# Sheet_1_2026-02-17_1.net
KiCad netlist of a schematic drawn in Altium Designer
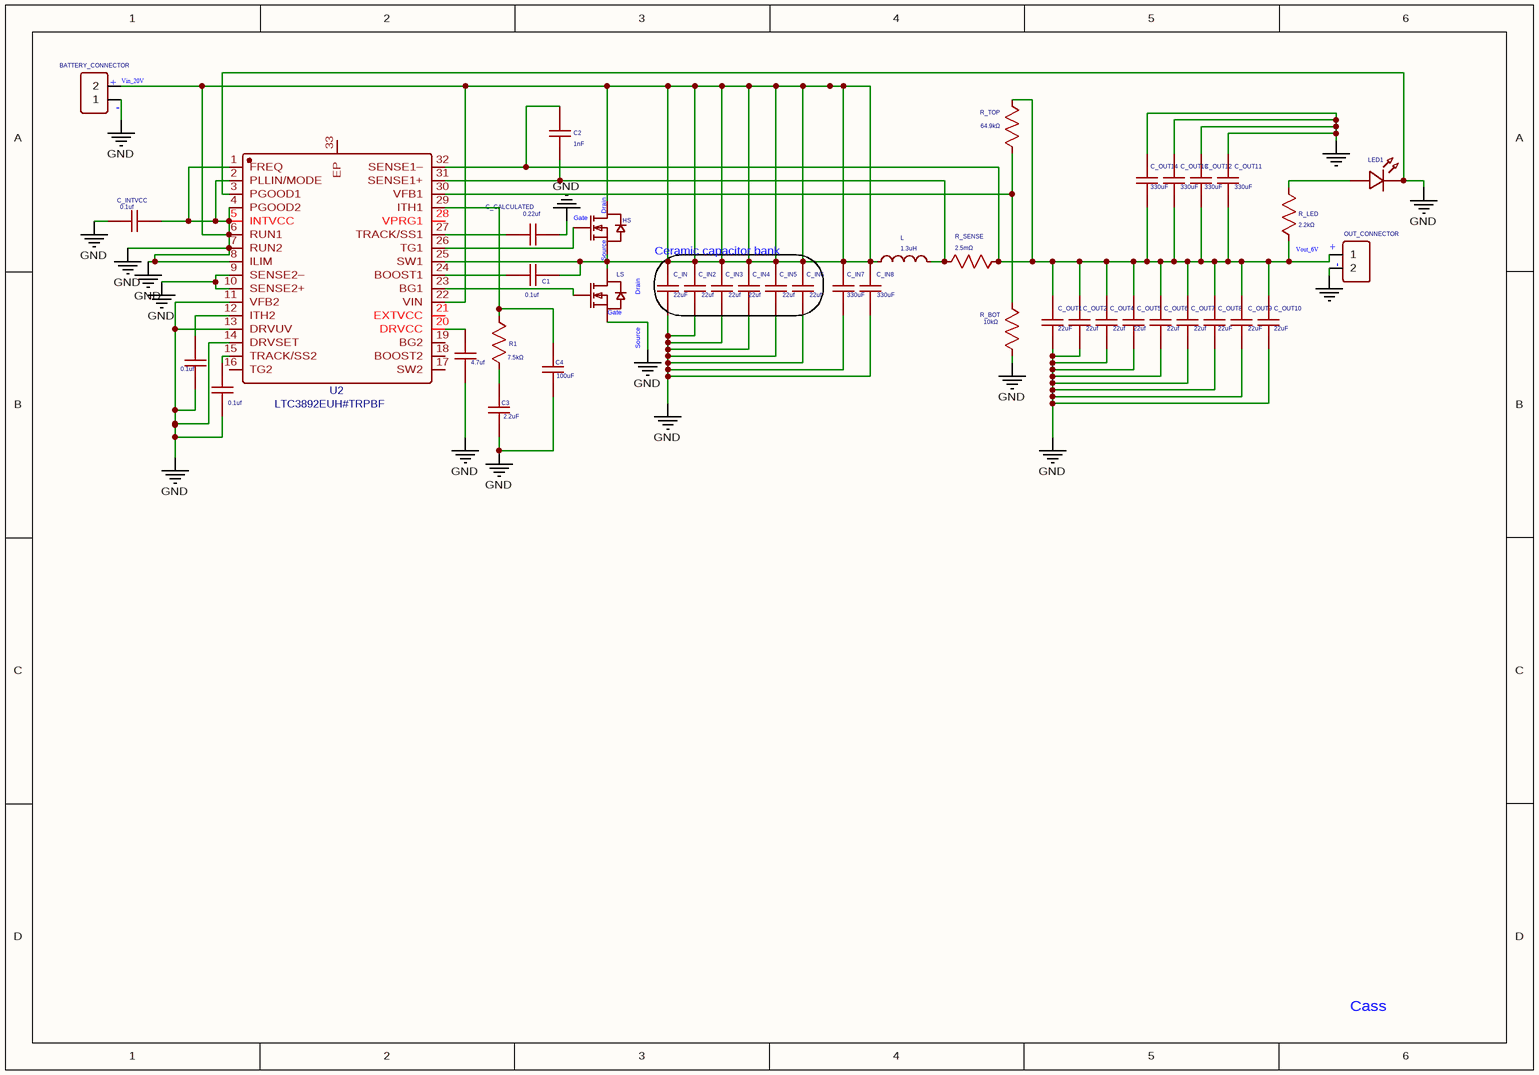
[diagram p0: Sheet_1_2026-02-17 (1).schdoc]

(export (version "E")
  (design (tool "Eeschema 10.0.6"))
  (components
    (comp (ref "BATTERY_CONNECTOR")
      (value "CONN-TH_2P-P5.00")
      (footprint "CONN-TH_2P-P5.00")
      (fields (field (name "CONTRIBUTOR") "LCEDA_Lib"))
      (libsource (lib "altium-import") (part "root_2_CONN-TH_2P-P5.00_"))
    )
    (comp (ref "C1")
      (value "0.1uf")
      (footprint "C0603")
      (fields (field (name "CONTRIBUTOR") "LCEDA_Lib"))
      (libsource (lib "altium-import") (part "root_2_0.1uf_"))
    )
    (comp (ref "C2")
      (value "1nF")
      (footprint "C0603")
      (fields (field (name "CONTRIBUTOR") "LCEDA_Lib"))
      (libsource (lib "altium-import") (part "root_1_1nF_"))
    )
    (comp (ref "C3")
      (value "2.2uF")
      (footprint "C0603")
      (fields (field (name "CONTRIBUTOR") "LCEDA_Lib"))
      (libsource (lib "altium-import") (part "root_1_2.2uF_"))
    )
    (comp (ref "C4")
      (value "100uF")
      (footprint "C0603")
      (fields (field (name "CONTRIBUTOR") "LCEDA_Lib"))
      (libsource (lib "altium-import") (part "root_3_100uF_"))
    )
    (comp (ref "C_CALCULATED")
      (value "0.22uf")
      (footprint "C0603")
      (fields (field (name "CONTRIBUTOR") "LCEDA_Lib"))
      (libsource (lib "altium-import") (part "root_0_0.22uf_"))
    )
    (comp (ref "C_DRVCC")
      (value "4.7uf")
      (footprint "C0603")
      (fields (field (name "CONTRIBUTOR") "LCEDA_Lib"))
      (libsource (lib "altium-import") (part "root_1_4.7uf_"))
    )
    (comp (ref "C_IN")
      (value "22uF")
      (footprint "C0603")
      (fields (field (name "CONTRIBUTOR") "LCEDA_Lib"))
      (libsource (lib "altium-import") (part "root_1_22uF_"))
    )
    (comp (ref "C_IN2")
      (value "22uf")
      (footprint "C0603")
      (fields (field (name "CONTRIBUTOR") "LCEDA_Lib"))
      (libsource (lib "altium-import") (part "root_1_22uf_"))
    )
    (comp (ref "C_IN3")
      (value "22uf")
      (footprint "C0603")
      (fields (field (name "CONTRIBUTOR") "LCEDA_Lib"))
      (libsource (lib "altium-import") (part "root_1_22uf_"))
    )
    (comp (ref "C_IN4")
      (value "22uf")
      (footprint "C0603")
      (fields (field (name "CONTRIBUTOR") "LCEDA_Lib"))
      (libsource (lib "altium-import") (part "root_1_22uf_"))
    )
    (comp (ref "C_IN5")
      (value "22uf")
      (footprint "C0603")
      (fields (field (name "CONTRIBUTOR") "LCEDA_Lib"))
      (libsource (lib "altium-import") (part "root_1_22uf_"))
    )
    (comp (ref "C_IN6")
      (value "22uf")
      (footprint "C0603")
      (fields (field (name "CONTRIBUTOR") "LCEDA_Lib"))
      (libsource (lib "altium-import") (part "root_1_22uf_"))
    )
    (comp (ref "C_IN7")
      (value "330uF")
      (footprint "C0603")
      (fields (field (name "CONTRIBUTOR") "LCEDA_Lib"))
      (libsource (lib "altium-import") (part "root_1_330uF_"))
    )
    (comp (ref "C_IN8")
      (value "330uF")
      (footprint "C0603")
      (fields (field (name "CONTRIBUTOR") "LCEDA_Lib"))
      (libsource (lib "altium-import") (part "root_1_330uF_"))
    )
    (comp (ref "C_INTVCC")
      (value "0.1uf")
      (footprint "C0603")
      (fields (field (name "CONTRIBUTOR") "LCEDA_Lib"))
      (libsource (lib "altium-import") (part "root_2_0.1uf_"))
    )
    (comp (ref "C_INTVCC1")
      (value "0.1uf")
      (footprint "C0603")
      (fields (field (name "CONTRIBUTOR") "LCEDA_Lib"))
      (libsource (lib "altium-import") (part "root_3_0.1uf_"))
    )
    (comp (ref "C_INTVCC2")
      (value "0.1uf")
      (footprint "C0603")
      (fields (field (name "CONTRIBUTOR") "LCEDA_Lib"))
      (libsource (lib "altium-import") (part "root_1_0.1uf_"))
    )
    (comp (ref "C_OUT1")
      (value "22uF")
      (footprint "C0603")
      (fields (field (name "CONTRIBUTOR") "LCEDA_Lib"))
      (libsource (lib "altium-import") (part "root_1_22uF_"))
    )
    (comp (ref "C_OUT2")
      (value "22uf")
      (footprint "C0603")
      (fields (field (name "CONTRIBUTOR") "LCEDA_Lib"))
      (libsource (lib "altium-import") (part "root_1_22uf_"))
    )
    (comp (ref "C_OUT4")
      (value "22uf")
      (footprint "C0603")
      (fields (field (name "CONTRIBUTOR") "LCEDA_Lib"))
      (libsource (lib "altium-import") (part "root_1_22uf_"))
    )
    (comp (ref "C_OUT5")
      (value "22uf")
      (footprint "C0603")
      (fields (field (name "CONTRIBUTOR") "LCEDA_Lib"))
      (libsource (lib "altium-import") (part "root_1_22uf_"))
    )
    (comp (ref "C_OUT6")
      (value "22uf")
      (footprint "C0603")
      (fields (field (name "CONTRIBUTOR") "LCEDA_Lib"))
      (libsource (lib "altium-import") (part "root_1_22uf_"))
    )
    (comp (ref "C_OUT7")
      (value "22uf")
      (footprint "C0603")
      (fields (field (name "CONTRIBUTOR") "LCEDA_Lib"))
      (libsource (lib "altium-import") (part "root_1_22uf_"))
    )
    (comp (ref "C_OUT8")
      (value "22uF")
      (footprint "C0603")
      (fields (field (name "CONTRIBUTOR") "LCEDA_Lib"))
      (libsource (lib "altium-import") (part "root_1_22uF_"))
    )
    (comp (ref "C_OUT9")
      (value "22uF")
      (footprint "C0603")
      (fields (field (name "CONTRIBUTOR") "LCEDA_Lib"))
      (libsource (lib "altium-import") (part "root_1_22uF_"))
    )
    (comp (ref "C_OUT10")
      (value "22uF")
      (footprint "C0603")
      (fields (field (name "CONTRIBUTOR") "LCEDA_Lib"))
      (libsource (lib "altium-import") (part "root_1_22uF_"))
    )
    (comp (ref "C_OUT11")
      (value "330uF")
      (footprint "C0603")
      (fields (field (name "CONTRIBUTOR") "LCEDA_Lib"))
      (libsource (lib "altium-import") (part "root_1_330uF_"))
    )
    (comp (ref "C_OUT12")
      (value "330uF")
      (footprint "C0603")
      (fields (field (name "CONTRIBUTOR") "LCEDA_Lib"))
      (libsource (lib "altium-import") (part "root_1_330uF_"))
    )
    (comp (ref "C_OUT13")
      (value "330uF")
      (footprint "C0603")
      (fields (field (name "CONTRIBUTOR") "LCEDA_Lib"))
      (libsource (lib "altium-import") (part "root_1_330uF_"))
    )
    (comp (ref "C_OUT14")
      (value "330uF")
      (footprint "C0603")
      (fields (field (name "CONTRIBUTOR") "LCEDA_Lib"))
      (libsource (lib "altium-import") (part "root_1_330uF_"))
    )
    (comp (ref "HS")
      (value "2N7002")
      (footprint "SOT-23_L2.9-W1.3-P0.95-LS2.4-BR")
      (fields
        (field (name "MANUFACTURER") "Nexperia")
        (field (name "MANUFACTURER PART") "2N7002,215")
        (field (name "CONTRIBUTOR") "LCEDA_Lib")
      )
      (libsource (lib "altium-import") (part "root_0_2N7002_"))
    )
    (comp (ref "L")
      (value "1.3uH")
      (footprint "L0603")
      (fields (field (name "CONTRIBUTOR") "LCEDA_Lib"))
      (libsource (lib "altium-import") (part "root_0_1.3uH_"))
    )
    (comp (ref "LED1")
      (value "LED-0603_B")
      (footprint "LED0603_BLUE")
      (fields
        (field (name "MANUFACTURER") "EVERLIGHT(台湾亿光)")
        (field (name "MANUFACTURER PART") "19-217/BHC-ZL1M2RY/3T")
        (field (name "CONTRIBUTOR") "LCEDA_01")
      )
      (libsource (lib "altium-import") (part "root_0_LED-0603_B_"))
    )
    (comp (ref "LS")
      (value "2N7002")
      (footprint "SOT-23_L2.9-W1.3-P0.95-LS2.4-BR")
      (fields
        (field (name "MANUFACTURER") "Nexperia")
        (field (name "MANUFACTURER PART") "2N7002,215")
        (field (name "CONTRIBUTOR") "LCEDA_Lib")
      )
      (libsource (lib "altium-import") (part "root_0_2N7002_"))
    )
    (comp (ref "OUT_CONNECTOR")
      (value "CONN-TH_2P-P5.00")
      (footprint "CONN-TH_2P-P5.00")
      (fields (field (name "CONTRIBUTOR") "LCEDA_Lib"))
      (libsource (lib "altium-import") (part "root_0_CONN-TH_2P-P5.00_"))
    )
    (comp (ref "R1")
      (value "7.5kΩ")
      (footprint "R0603")
      (fields (field (name "CONTRIBUTOR") "LCEDA_Lib"))
      (libsource (lib "altium-import") (part "root_1_7.5kΩ_"))
    )
    (comp (ref "R_BOT")
      (value "10kΩ")
      (footprint "R0603")
      (fields (field (name "CONTRIBUTOR") "LCEDA_Lib"))
      (libsource (lib "altium-import") (part "root_3_10kΩ_"))
    )
    (comp (ref "R_LED")
      (value "2.2kΩ")
      (footprint "R0603")
      (fields (field (name "CONTRIBUTOR") "LCEDA_Lib"))
      (libsource (lib "altium-import") (part "root_1_2.2kΩ_"))
    )
    (comp (ref "R_SENSE")
      (value "2.5mΩ")
      (footprint "R0603")
      (fields (field (name "CONTRIBUTOR") "LCEDA_Lib"))
      (libsource (lib "altium-import") (part "root_2_2.5mΩ_"))
    )
    (comp (ref "R_TOP")
      (value "64.9kΩ")
      (footprint "R0603")
      (fields (field (name "CONTRIBUTOR") "LCEDA_Lib"))
      (libsource (lib "altium-import") (part "root_3_64.9kΩ_"))
    )
    (comp (ref "U2")
      (value "LTC3892EUH#TRPBF")
      (footprint "QFN-32_L5.0-W5.0-P0.50-TL-EP3.5")
      (fields (field (name "MANUFACTURER") "ADI(亚德诺)") (field (name "CONTRIBUTOR") "LCSC"))
      (libsource (lib "altium-import") (part "root_0_LTC3892EUH#TRPBF_"))
    )
  )
  (nets
    (net (code "2") (name "GND") (class "Default")
      (node (ref "BATTERY_CONNECTOR") (pin "1") (pinfunction "1_1") (pintype "passive"))
      (node (ref "BATTERY_CONNECTOR") (pin "2") (pinfunction "2_2") (pintype "passive"))
      (node (ref "C1") (pin "1") (pinfunction "1_1") (pintype "passive"))
      (node (ref "C2") (pin "2") (pinfunction "2_2") (pintype "passive"))
      (node (ref "C3") (pin "1") (pinfunction "1_1") (pintype "passive"))
      (node (ref "C4") (pin "2") (pinfunction "2_2") (pintype "passive"))
      (node (ref "C_CALCULATED") (pin "2") (pinfunction "2_2") (pintype "passive"))
      (node (ref "C_DRVCC") (pin "1") (pinfunction "1_1") (pintype "passive"))
      (node (ref "C_IN") (pin "1") (pinfunction "1_1") (pintype "passive"))
      (node (ref "C_IN") (pin "2") (pinfunction "2_2") (pintype "passive"))
      (node (ref "C_IN2") (pin "1") (pinfunction "1_1") (pintype "passive"))
      (node (ref "C_IN2") (pin "2") (pinfunction "2_2") (pintype "passive"))
      (node (ref "C_IN3") (pin "1") (pinfunction "1_1") (pintype "passive"))
      (node (ref "C_IN3") (pin "2") (pinfunction "2_2") (pintype "passive"))
      (node (ref "C_IN4") (pin "1") (pinfunction "1_1") (pintype "passive"))
      (node (ref "C_IN4") (pin "2") (pinfunction "2_2") (pintype "passive"))
      (node (ref "C_IN5") (pin "1") (pinfunction "1_1") (pintype "passive"))
      (node (ref "C_IN5") (pin "2") (pinfunction "2_2") (pintype "passive"))
      (node (ref "C_IN6") (pin "1") (pinfunction "1_1") (pintype "passive"))
      (node (ref "C_IN6") (pin "2") (pinfunction "2_2") (pintype "passive"))
      (node (ref "C_IN7") (pin "1") (pinfunction "1_1") (pintype "passive"))
      (node (ref "C_IN7") (pin "2") (pinfunction "2_2") (pintype "passive"))
      (node (ref "C_IN8") (pin "1") (pinfunction "1_1") (pintype "passive"))
      (node (ref "C_IN8") (pin "2") (pinfunction "2_2") (pintype "passive"))
      (node (ref "C_INTVCC") (pin "1") (pinfunction "1_1") (pintype "passive"))
      (node (ref "C_INTVCC") (pin "2") (pinfunction "2_2") (pintype "passive"))
      (node (ref "C_INTVCC1") (pin "2") (pinfunction "2_2") (pintype "passive"))
      (node (ref "C_INTVCC2") (pin "1") (pinfunction "1_1") (pintype "passive"))
      (node (ref "C_OUT1") (pin "1") (pinfunction "1_1") (pintype "passive"))
      (node (ref "C_OUT1") (pin "2") (pinfunction "2_2") (pintype "passive"))
      (node (ref "C_OUT10") (pin "1") (pinfunction "1_1") (pintype "passive"))
      (node (ref "C_OUT10") (pin "2") (pinfunction "2_2") (pintype "passive"))
      (node (ref "C_OUT11") (pin "1") (pinfunction "1_1") (pintype "passive"))
      (node (ref "C_OUT11") (pin "2") (pinfunction "2_2") (pintype "passive"))
      (node (ref "C_OUT12") (pin "1") (pinfunction "1_1") (pintype "passive"))
      (node (ref "C_OUT12") (pin "2") (pinfunction "2_2") (pintype "passive"))
      (node (ref "C_OUT13") (pin "1") (pinfunction "1_1") (pintype "passive"))
      (node (ref "C_OUT13") (pin "2") (pinfunction "2_2") (pintype "passive"))
      (node (ref "C_OUT14") (pin "1") (pinfunction "1_1") (pintype "passive"))
      (node (ref "C_OUT14") (pin "2") (pinfunction "2_2") (pintype "passive"))
      (node (ref "C_OUT2") (pin "1") (pinfunction "1_1") (pintype "passive"))
      (node (ref "C_OUT2") (pin "2") (pinfunction "2_2") (pintype "passive"))
      (node (ref "C_OUT4") (pin "1") (pinfunction "1_1") (pintype "passive"))
      (node (ref "C_OUT4") (pin "2") (pinfunction "2_2") (pintype "passive"))
      (node (ref "C_OUT5") (pin "1") (pinfunction "1_1") (pintype "passive"))
      (node (ref "C_OUT5") (pin "2") (pinfunction "2_2") (pintype "passive"))
      (node (ref "C_OUT6") (pin "1") (pinfunction "1_1") (pintype "passive"))
      (node (ref "C_OUT6") (pin "2") (pinfunction "2_2") (pintype "passive"))
      (node (ref "C_OUT7") (pin "1") (pinfunction "1_1") (pintype "passive"))
      (node (ref "C_OUT7") (pin "2") (pinfunction "2_2") (pintype "passive"))
      (node (ref "C_OUT8") (pin "1") (pinfunction "1_1") (pintype "passive"))
      (node (ref "C_OUT8") (pin "2") (pinfunction "2_2") (pintype "passive"))
      (node (ref "C_OUT9") (pin "1") (pinfunction "1_1") (pintype "passive"))
      (node (ref "C_OUT9") (pin "2") (pinfunction "2_2") (pintype "passive"))
      (node (ref "HS") (pin "2") (pinfunction "S_2") (pintype "passive"))
      (node (ref "HS") (pin "3") (pinfunction "D_3") (pintype "passive"))
      (node (ref "L") (pin "1") (pinfunction "1_1") (pintype "passive"))
      (node (ref "LED1") (pin "2") (pinfunction "2_2") (pintype "passive"))
      (node (ref "LS") (pin "2") (pinfunction "S_2") (pintype "passive"))
      (node (ref "LS") (pin "3") (pinfunction "D_3") (pintype "passive"))
      (node (ref "OUT_CONNECTOR") (pin "1") (pinfunction "1_1") (pintype "passive"))
      (node (ref "OUT_CONNECTOR") (pin "2") (pinfunction "2_2") (pintype "passive"))
      (node (ref "R_BOT") (pin "2") (pinfunction "2_2") (pintype "passive"))
      (node (ref "R_LED") (pin "1") (pinfunction "1_1") (pintype "passive"))
      (node (ref "R_SENSE") (pin "1") (pinfunction "1_1") (pintype "passive"))
      (node (ref "R_TOP") (pin "1") (pinfunction "1_1") (pintype "passive"))
      (node (ref "U2") (pin "1") (pinfunction "FREQ_1") (pintype "passive"))
      (node (ref "U2") (pin "10") (pinfunction "SENSE2+_10") (pintype "passive"))
      (node (ref "U2") (pin "11") (pinfunction "VFB2_11") (pintype "passive"))
      (node (ref "U2") (pin "13") (pinfunction "DRVUV_13") (pintype "passive"))
      (node (ref "U2") (pin "14") (pinfunction "DRVSET_14") (pintype "passive"))
      (node (ref "U2") (pin "2") (pinfunction "PLLIN/MODE_2") (pintype "passive"))
      (node (ref "U2") (pin "22") (pinfunction "VIN_22") (pintype "passive"))
      (node (ref "U2") (pin "25") (pinfunction "SW1_25") (pintype "passive"))
      (node (ref "U2") (pin "3") (pinfunction "PGOOD1_3") (pintype "passive"))
      (node (ref "U2") (pin "32") (pinfunction "SENSE1–_32") (pintype "passive"))
      (node (ref "U2") (pin "4") (pinfunction "PGOOD2_4") (pintype "passive"))
      (node (ref "U2") (pin "5") (pinfunction "INTVCC_5") (pintype "passive"))
      (node (ref "U2") (pin "6") (pinfunction "RUN1_6") (pintype "passive"))
      (node (ref "U2") (pin "7") (pinfunction "RUN2_7") (pintype "passive"))
      (node (ref "U2") (pin "8") (pinfunction "ILIM_8") (pintype "passive"))
      (node (ref "U2") (pin "9") (pinfunction "SENSE2–_9") (pintype "passive"))
    )
    (net (code "3") (name "Net-(C3-Pad2)") (class "Default")
      (node (ref "C3") (pin "2") (pinfunction "2_2") (pintype "passive"))
      (node (ref "R1") (pin "1") (pinfunction "1_1") (pintype "passive"))
    )
    (net (code "4") (name "Net-(HS-G)") (class "Default")
      (node (ref "HS") (pin "1") (pinfunction "G_1") (pintype "passive"))
      (node (ref "U2") (pin "26") (pinfunction "TG1_26") (pintype "passive"))
    )
    (net (code "5") (name "Net-(LED1-Pad1)") (class "Default")
      (node (ref "LED1") (pin "1") (pinfunction "1_1") (pintype "passive"))
      (node (ref "R_LED") (pin "2") (pinfunction "2_2") (pintype "passive"))
    )
    (net (code "6") (name "Net-(LS-G)") (class "Default")
      (node (ref "LS") (pin "1") (pinfunction "G_1") (pintype "passive"))
      (node (ref "U2") (pin "23") (pinfunction "BG1_23") (pintype "passive"))
    )
    (net (code "7") (name "Net-(U2-BOOST1)") (class "Default")
      (node (ref "C1") (pin "2") (pinfunction "2_2") (pintype "passive"))
      (node (ref "U2") (pin "24") (pinfunction "BOOST1_24") (pintype "passive"))
    )
    (net (code "8") (name "Net-(U2-DRVCC)") (class "Default")
      (node (ref "C_DRVCC") (pin "2") (pinfunction "2_2") (pintype "passive"))
      (node (ref "U2") (pin "20") (pinfunction "DRVCC_20") (pintype "passive"))
    )
    (net (code "9") (name "Net-(U2-ITH1)") (class "Default")
      (node (ref "C4") (pin "1") (pinfunction "1_1") (pintype "passive"))
      (node (ref "R1") (pin "2") (pinfunction "2_2") (pintype "passive"))
      (node (ref "U2") (pin "29") (pinfunction "ITH1_29") (pintype "passive"))
    )
    (net (code "10") (name "Net-(U2-ITH2)") (class "Default")
      (node (ref "C_INTVCC2") (pin "2") (pinfunction "2_2") (pintype "passive"))
      (node (ref "U2") (pin "12") (pinfunction "ITH2_12") (pintype "passive"))
    )
    (net (code "11") (name "Net-(U2-SENSE1+)") (class "Default")
      (node (ref "C2") (pin "1") (pinfunction "1_1") (pintype "passive"))
      (node (ref "L") (pin "2") (pinfunction "2_2") (pintype "passive"))
      (node (ref "R_SENSE") (pin "2") (pinfunction "2_2") (pintype "passive"))
      (node (ref "U2") (pin "31") (pinfunction "SENSE1+_31") (pintype "passive"))
    )
    (net (code "12") (name "Net-(U2-TRACK{slash}SS1)") (class "Default")
      (node (ref "C_CALCULATED") (pin "1") (pinfunction "1_1") (pintype "passive"))
      (node (ref "U2") (pin "27") (pinfunction "TRACK/SS1_27") (pintype "passive"))
    )
    (net (code "13") (name "Net-(U2-TRACK{slash}SS2)") (class "Default")
      (node (ref "C_INTVCC1") (pin "1") (pinfunction "1_1") (pintype "passive"))
      (node (ref "U2") (pin "15") (pinfunction "TRACK/SS2_15") (pintype "passive"))
    )
    (net (code "14") (name "Net-(U2-VFB1)") (class "Default")
      (node (ref "R_BOT") (pin "1") (pinfunction "1_1") (pintype "passive"))
      (node (ref "R_TOP") (pin "2") (pinfunction "2_2") (pintype "passive"))
      (node (ref "U2") (pin "30") (pinfunction "VFB1_30") (pintype "passive"))
    )
    (net (code "15") (name "unconnected-(U2-BG2-Pad19)") (class "Default")
      (node (ref "U2") (pin "19") (pinfunction "BG2_19") (pintype "passive"))
    )
    (net (code "16") (name "unconnected-(U2-BOOST2-Pad18)") (class "Default")
      (node (ref "U2") (pin "18") (pinfunction "BOOST2_18") (pintype "passive"))
    )
    (net (code "17") (name "unconnected-(U2-EP-Pad33)") (class "Default")
      (node (ref "U2") (pin "33") (pinfunction "EP_33") (pintype "passive"))
    )
    (net (code "18") (name "unconnected-(U2-EXTVCC-Pad21)") (class "Default")
      (node (ref "U2") (pin "21") (pinfunction "EXTVCC_21") (pintype "passive"))
    )
    (net (code "19") (name "unconnected-(U2-SW2-Pad17)") (class "Default")
      (node (ref "U2") (pin "17") (pinfunction "SW2_17") (pintype "passive"))
    )
    (net (code "20") (name "unconnected-(U2-TG2-Pad16)") (class "Default")
      (node (ref "U2") (pin "16") (pinfunction "TG2_16") (pintype "passive"))
    )
    (net (code "21") (name "unconnected-(U2-VPRG1-Pad28)") (class "Default")
      (node (ref "U2") (pin "28") (pinfunction "VPRG1_28") (pintype "passive"))
    )
  )
)
